# main_control.net
KiCad netlist of a schematic drawn in Altium Designer
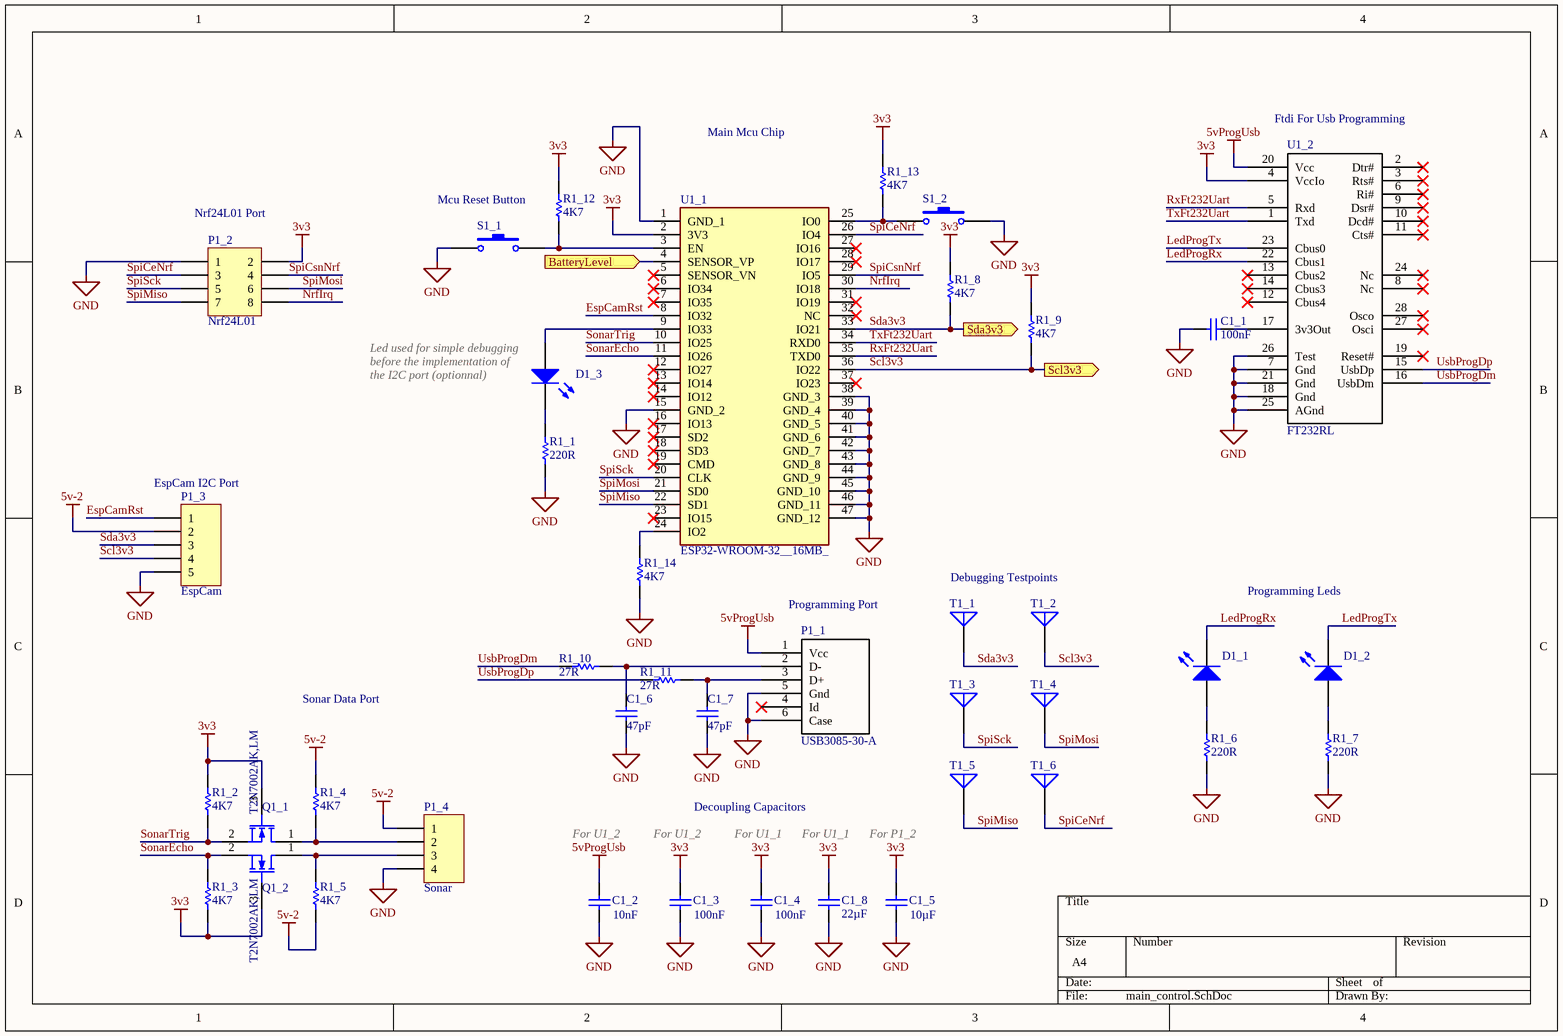
[diagram p0: main_control.SchDoc]

(export (version "E")
  (design (tool "Eeschema 10.0.6"))
  (components
    (comp (ref "C1_1")
      (value "100nF")
      (footprint "C1206")
      (description "Capacitor")
      (fields (field (name "Comment") "12063C104MAT2A") (field (name "PUBLISHER") "Altium Limited"))
      (libsource (lib "Miscellaneous Devices") (part "Cap"))
    )
    (comp (ref "C1_2")
      (value "10nF")
      (footprint "C1206")
      (description "Capacitor")
      (fields (field (name "Comment") "C1206C103M5RACTU") (field (name "PUBLISHER") "Altium Limited"))
      (libsource (lib "Miscellaneous Devices") (part "Cap"))
    )
    (comp (ref "C1_3")
      (value "100nF")
      (footprint "C1206")
      (description "Capacitor")
      (fields (field (name "Comment") "12063C104MAT2A") (field (name "PUBLISHER") "Altium Limited"))
      (libsource (lib "Miscellaneous Devices") (part "Cap"))
    )
    (comp (ref "C1_4")
      (value "100nF")
      (footprint "C1206")
      (description "Capacitor")
      (fields (field (name "Comment") "12063C104MAT2A") (field (name "PUBLISHER") "Altium Limited"))
      (libsource (lib "Miscellaneous Devices") (part "Cap"))
    )
    (comp (ref "C1_5")
      (value "10µF")
      (footprint "C1206")
      (description "Capacitor")
      (fields (field (name "Comment") "EMK316BJ106MLHT") (field (name "PUBLISHER") "Altium Limited"))
      (libsource (lib "Miscellaneous Devices") (part "Cap"))
    )
    (comp (ref "C1_6")
      (value "47pF")
      (footprint "C1206")
      (description "Capacitor")
      (fields (field (name "Comment") "CML1206C0G470JT50V") (field (name "PUBLISHER") "Altium Limited"))
      (libsource (lib "Miscellaneous Devices") (part "Cap"))
    )
    (comp (ref "C1_7")
      (value "47pF")
      (footprint "C1206")
      (description "Capacitor")
      (fields (field (name "Comment") "CML1206C0G470JT50V") (field (name "PUBLISHER") "Altium Limited"))
      (libsource (lib "Miscellaneous Devices") (part "Cap"))
    )
    (comp (ref "C1_8")
      (value "22µF")
      (footprint "C1206")
      (description "Capacitor")
      (fields (field (name "Comment") "CL31A226KOHNNNE") (field (name "PUBLISHER") "Altium Limited"))
      (libsource (lib "Miscellaneous Devices") (part "Cap"))
    )
    (comp (ref "D1_1")
      (value "LTST-C230KRKT")
      (footprint "C1206-POLARIZED")
      (description "Typical INFRARED GaAs LED")
      (fields (field (name "PUBLISHER") "Altium Limited"))
      (libsource (lib "Miscellaneous Devices") (part "LED0"))
    )
    (comp (ref "D1_2")
      (value "LTST-C230KRKT")
      (footprint "C1206-POLARIZED")
      (description "Typical INFRARED GaAs LED")
      (fields (field (name "PUBLISHER") "Altium Limited"))
      (libsource (lib "Miscellaneous Devices") (part "LED0"))
    )
    (comp (ref "D1_3")
      (value "APT3216QBC/D")
      (footprint "C1206-POLARIZED")
      (description "Typical INFRARED GaAs LED")
      (fields (field (name "PUBLISHER") "Altium Limited"))
      (libsource (lib "Miscellaneous Devices") (part "LED0"))
    )
    (comp (ref "P1_1")
      (value "USB3085-30-A")
      (footprint "USB-MICRO-CONNECTOR")
      (libsource (lib "projet_6e_session") (part "Usb Connector"))
    )
    (comp (ref "P1_2")
      (value "Nrf24L01")
      (footprint "HDR2X4-42")
      (description "Header, 4-Pin, Dual row")
      (fields (field (name "PUBLISHER") "Altium Limited"))
      (libsource (lib "Miscellaneous Connectors") (part "Header 4X2"))
    )
    (comp (ref "P1_3")
      (value "EspCam")
      (footprint "HDR1X5-42")
      (description "Header, 5-Pin")
      (fields (field (name "PUBLISHER") "Altium Limited"))
      (libsource (lib "Miscellaneous Connectors") (part "Header 5"))
    )
    (comp (ref "P1_4")
      (value "Sonar")
      (footprint "HDR1X4-42")
      (description "Header, 4-Pin")
      (fields (field (name "PUBLISHER") "Altium Limited"))
      (libsource (lib "Miscellaneous Connectors") (part "Header 4"))
    )
    (comp (ref "Q1_1")
      (value "T2N7002AK,LM")
      (footprint "SOT23_L")
      (description "N-Channel MOSFET")
      (fields (field (name "PUBLISHER") "Altium Limited"))
      (libsource (lib "Miscellaneous Devices") (part "MOSFET-N"))
    )
    (comp (ref "Q1_2")
      (value "T2N7002AK,LM")
      (footprint "SOT23_L")
      (description "N-Channel MOSFET")
      (fields (field (name "PUBLISHER") "Altium Limited"))
      (libsource (lib "Miscellaneous Devices") (part "MOSFET-N"))
    )
    (comp (ref "R1_1")
      (value "220R")
      (footprint "C1206")
      (description "Resistor")
      (fields (field (name "Comment") "Res1") (field (name "PUBLISHER") "Altium Limited"))
      (libsource (lib "Miscellaneous Devices") (part "Res1"))
    )
    (comp (ref "R1_2")
      (value "4K7")
      (footprint "C1206")
      (description "Resistor")
      (fields (field (name "Comment") "Res1") (field (name "PUBLISHER") "Altium Limited"))
      (libsource (lib "Miscellaneous Devices") (part "Res1"))
    )
    (comp (ref "R1_3")
      (value "4K7")
      (footprint "C1206")
      (description "Resistor")
      (fields (field (name "Comment") "Res1") (field (name "PUBLISHER") "Altium Limited"))
      (libsource (lib "Miscellaneous Devices") (part "Res1"))
    )
    (comp (ref "R1_4")
      (value "4K7")
      (footprint "C1206")
      (description "Resistor")
      (fields (field (name "Comment") "Res1") (field (name "PUBLISHER") "Altium Limited"))
      (libsource (lib "Miscellaneous Devices") (part "Res1"))
    )
    (comp (ref "R1_5")
      (value "4K7")
      (footprint "C1206")
      (description "Resistor")
      (fields (field (name "Comment") "Res1") (field (name "PUBLISHER") "Altium Limited"))
      (libsource (lib "Miscellaneous Devices") (part "Res1"))
    )
    (comp (ref "R1_6")
      (value "220R")
      (footprint "C1206")
      (description "Resistor")
      (fields (field (name "Comment") "Res1") (field (name "PUBLISHER") "Altium Limited"))
      (libsource (lib "Miscellaneous Devices") (part "Res1"))
    )
    (comp (ref "R1_7")
      (value "220R")
      (footprint "C1206")
      (description "Resistor")
      (fields (field (name "Comment") "Res1") (field (name "PUBLISHER") "Altium Limited"))
      (libsource (lib "Miscellaneous Devices") (part "Res1"))
    )
    (comp (ref "R1_8")
      (value "4K7")
      (footprint "C1206")
      (description "Resistor")
      (fields (field (name "Comment") "Res1") (field (name "PUBLISHER") "Altium Limited"))
      (libsource (lib "Miscellaneous Devices") (part "Res1"))
    )
    (comp (ref "R1_9")
      (value "4K7")
      (footprint "C1206")
      (description "Resistor")
      (fields (field (name "Comment") "Res1") (field (name "PUBLISHER") "Altium Limited"))
      (libsource (lib "Miscellaneous Devices") (part "Res1"))
    )
    (comp (ref "R1_10")
      (value "27R")
      (footprint "C1206")
      (description "Resistor")
      (fields (field (name "Comment") "Res1") (field (name "PUBLISHER") "Altium Limited"))
      (libsource (lib "Miscellaneous Devices") (part "Res1"))
    )
    (comp (ref "R1_11")
      (value "27R")
      (footprint "C1206")
      (description "Resistor")
      (fields (field (name "Comment") "Res1") (field (name "PUBLISHER") "Altium Limited"))
      (libsource (lib "Miscellaneous Devices") (part "Res1"))
    )
    (comp (ref "R1_12")
      (value "4K7")
      (footprint "C1206")
      (description "Resistor")
      (fields (field (name "Comment") "Res1") (field (name "PUBLISHER") "Altium Limited"))
      (libsource (lib "Miscellaneous Devices") (part "Res1"))
    )
    (comp (ref "R1_13")
      (value "4K7")
      (footprint "C1206")
      (description "Resistor")
      (fields (field (name "Comment") "Res1") (field (name "PUBLISHER") "Altium Limited"))
      (libsource (lib "Miscellaneous Devices") (part "Res1"))
    )
    (comp (ref "R1_14")
      (value "4K7")
      (footprint "C1206")
      (description "Resistor")
      (fields (field (name "Comment") "Res1") (field (name "PUBLISHER") "Altium Limited"))
      (libsource (lib "Miscellaneous Devices") (part "Res1"))
    )
    (comp (ref "S1_1")
      (value "FSM4LPASTR")
      (footprint "SW4-SMT")
      (description "Switch")
      (fields (field (name "PUBLISHER") "Altium Limited"))
      (libsource (lib "Miscellaneous Devices") (part "SW-PB"))
    )
    (comp (ref "S1_2")
      (value "FSM4LPASTR")
      (footprint "SW4-SMT")
      (description "Switch")
      (fields (field (name "PUBLISHER") "Altium Limited"))
      (libsource (lib "Miscellaneous Devices") (part "SW-PB"))
    )
    (comp (ref "T1_1")
      (value "Mounting Hole")
      (footprint "TESTPOINT")
      (description "Generic Antenna")
      (fields (field (name "PUBLISHER") "Altium Limited"))
      (libsource (lib "Miscellaneous Devices") (part "Antenna"))
    )
    (comp (ref "T1_2")
      (value "Mounting Hole")
      (footprint "TESTPOINT")
      (description "Generic Antenna")
      (fields (field (name "PUBLISHER") "Altium Limited"))
      (libsource (lib "Miscellaneous Devices") (part "Antenna"))
    )
    (comp (ref "T1_3")
      (value "Mounting Hole")
      (footprint "TESTPOINT")
      (description "Generic Antenna")
      (fields (field (name "PUBLISHER") "Altium Limited"))
      (libsource (lib "Miscellaneous Devices") (part "Antenna"))
    )
    (comp (ref "T1_4")
      (value "Mounting Hole")
      (footprint "TESTPOINT")
      (description "Generic Antenna")
      (fields (field (name "PUBLISHER") "Altium Limited"))
      (libsource (lib "Miscellaneous Devices") (part "Antenna"))
    )
    (comp (ref "T1_5")
      (value "Mounting Hole")
      (footprint "TESTPOINT")
      (description "Generic Antenna")
      (fields (field (name "PUBLISHER") "Altium Limited"))
      (libsource (lib "Miscellaneous Devices") (part "Antenna"))
    )
    (comp (ref "T1_6")
      (value "Mounting Hole")
      (footprint "TESTPOINT")
      (description "Generic Antenna")
      (fields (field (name "PUBLISHER") "Altium Limited"))
      (libsource (lib "Miscellaneous Devices") (part "Antenna"))
    )
    (comp (ref "U1_1")
      (value "ESP32-WROOM-32__16MB_")
      (footprint "ESP32WROOM32D16MB")
      (description "Integrated Circuit")
      (fields
        (field (name "MANUFACTURER_PART_NUMBER") "ESP32-WROOM-32 (16MB)")
        (field (name "MOUSER PART NUMBER") "356-ESPWROOM3216MB")
      )
      (libsource (lib "*") (part "ESP32-WROOM-32__16MB_"))
    )
    (comp (ref "U1_2")
      (value "FT232RL")
      (footprint "SOP65P778X200-28N")
      (libsource (lib "projet 6e session") (part "Ft232"))
    )
  )
  (nets
    (net (code "1") (name "/BatteryLevel") (class "Default")
      (node (ref "U1_1") (pin "4") (pinfunction "SENSOR_VP_4") (pintype "passive"))
    )
    (net (code "2") (name "/EspCamRst") (class "Default")
      (node (ref "P1_3") (pin "1") (pinfunction "1_1") (pintype "passive"))
      (node (ref "U1_1") (pin "8") (pinfunction "IO32_8") (pintype "passive"))
    )
    (net (code "3") (name "/LedProgRx") (class "Default")
      (node (ref "D1_1") (pin "2") (pinfunction "K_2") (pintype "passive"))
      (node (ref "U1_2") (pin "22") (pinfunction "Cbus1_22") (pintype "passive"))
    )
    (net (code "4") (name "/LedProgTx") (class "Default")
      (node (ref "D1_2") (pin "2") (pinfunction "K_2") (pintype "passive"))
      (node (ref "U1_2") (pin "23") (pinfunction "Cbus0_23") (pintype "passive"))
    )
    (net (code "5") (name "/NrfIrq") (class "Default")
      (node (ref "P1_2") (pin "8") (pinfunction "8_8") (pintype "passive"))
      (node (ref "U1_1") (pin "30") (pinfunction "IO18_30") (pintype "passive"))
    )
    (net (code "6") (name "/RxFt232Uart") (class "Default")
      (node (ref "U1_1") (pin "35") (pinfunction "TXD0_35") (pintype "passive"))
      (node (ref "U1_2") (pin "5") (pinfunction "Rxd_5") (pintype "passive"))
    )
    (net (code "7") (name "/Scl3v3") (class "Default")
      (node (ref "P1_3") (pin "4") (pinfunction "4_4") (pintype "passive"))
      (node (ref "R1_9") (pin "2") (pinfunction "2_2") (pintype "passive"))
      (node (ref "T1_2") (pin "1") (pinfunction "A_1") (pintype "passive"))
      (node (ref "U1_1") (pin "36") (pinfunction "IO22_36") (pintype "passive"))
    )
    (net (code "8") (name "/Sda3v3") (class "Default")
      (node (ref "P1_3") (pin "3") (pinfunction "3_3") (pintype "passive"))
      (node (ref "R1_8") (pin "2") (pinfunction "2_2") (pintype "passive"))
      (node (ref "T1_1") (pin "1") (pinfunction "A_1") (pintype "passive"))
      (node (ref "U1_1") (pin "33") (pinfunction "IO21_33") (pintype "passive"))
    )
    (net (code "9") (name "/SonarEcho") (class "Default")
      (node (ref "Q1_2") (pin "2") (pinfunction "S_2") (pintype "passive"))
      (node (ref "R1_3") (pin "1") (pinfunction "1_1") (pintype "passive"))
      (node (ref "U1_1") (pin "11") (pinfunction "IO26_11") (pintype "passive"))
    )
    (net (code "10") (name "/SonarTrig") (class "Default")
      (node (ref "Q1_1") (pin "2") (pinfunction "S_2") (pintype "passive"))
      (node (ref "R1_2") (pin "2") (pinfunction "2_2") (pintype "passive"))
      (node (ref "U1_1") (pin "10") (pinfunction "IO25_10") (pintype "passive"))
    )
    (net (code "11") (name "/SpiCeNrf") (class "Default")
      (node (ref "P1_2") (pin "3") (pinfunction "3_3") (pintype "passive"))
      (node (ref "T1_6") (pin "1") (pinfunction "A_1") (pintype "passive"))
      (node (ref "U1_1") (pin "26") (pinfunction "IO4_26") (pintype "passive"))
    )
    (net (code "12") (name "/SpiCsnNrf") (class "Default")
      (node (ref "P1_2") (pin "4") (pinfunction "4_4") (pintype "passive"))
      (node (ref "U1_1") (pin "29") (pinfunction "IO5_29") (pintype "passive"))
    )
    (net (code "13") (name "/SpiMiso") (class "Default")
      (node (ref "P1_2") (pin "7") (pinfunction "7_7") (pintype "passive"))
      (node (ref "T1_5") (pin "1") (pinfunction "A_1") (pintype "passive"))
      (node (ref "U1_1") (pin "22") (pinfunction "SD1_22") (pintype "passive"))
    )
    (net (code "14") (name "/SpiMosi") (class "Default")
      (node (ref "P1_2") (pin "6") (pinfunction "6_6") (pintype "passive"))
      (node (ref "T1_4") (pin "1") (pinfunction "A_1") (pintype "passive"))
      (node (ref "U1_1") (pin "21") (pinfunction "SD0_21") (pintype "passive"))
    )
    (net (code "15") (name "/SpiSck") (class "Default")
      (node (ref "P1_2") (pin "5") (pinfunction "5_5") (pintype "passive"))
      (node (ref "T1_3") (pin "1") (pinfunction "A_1") (pintype "passive"))
      (node (ref "U1_1") (pin "20") (pinfunction "CLK_20") (pintype "passive"))
    )
    (net (code "16") (name "/TxFt232Uart") (class "Default")
      (node (ref "U1_1") (pin "34") (pinfunction "RXD0_34") (pintype "passive"))
      (node (ref "U1_2") (pin "1") (pinfunction "Txd_1") (pintype "passive"))
    )
    (net (code "17") (name "/UsbProgDm") (class "Default")
      (node (ref "R1_10") (pin "1") (pinfunction "1_1") (pintype "passive"))
      (node (ref "U1_2") (pin "16") (pinfunction "UsbDm_16") (pintype "passive"))
    )
    (net (code "18") (name "/UsbProgDp") (class "Default")
      (node (ref "R1_11") (pin "1") (pinfunction "1_1") (pintype "passive"))
      (node (ref "U1_2") (pin "15") (pinfunction "UsbDp_15") (pintype "passive"))
    )
    (net (code "19") (name "3v3") (class "Default")
      (node (ref "C1_3") (pin "1") (pinfunction "1_1") (pintype "passive"))
      (node (ref "C1_4") (pin "1") (pinfunction "1_1") (pintype "passive"))
      (node (ref "C1_5") (pin "1") (pinfunction "1_1") (pintype "passive"))
      (node (ref "C1_8") (pin "1") (pinfunction "1_1") (pintype "passive"))
      (node (ref "P1_2") (pin "2") (pinfunction "2_2") (pintype "passive"))
      (node (ref "Q1_1") (pin "3") (pinfunction "G_3") (pintype "passive"))
      (node (ref "Q1_2") (pin "3") (pinfunction "G_3") (pintype "passive"))
      (node (ref "R1_12") (pin "2") (pinfunction "2_2") (pintype "passive"))
      (node (ref "R1_13") (pin "1") (pinfunction "1_1") (pintype "passive"))
      (node (ref "R1_2") (pin "1") (pinfunction "1_1") (pintype "passive"))
      (node (ref "R1_3") (pin "2") (pinfunction "2_2") (pintype "passive"))
      (node (ref "R1_8") (pin "1") (pinfunction "1_1") (pintype "passive"))
      (node (ref "R1_9") (pin "1") (pinfunction "1_1") (pintype "passive"))
      (node (ref "U1_1") (pin "2") (pinfunction "3V3_2") (pintype "passive"))
      (node (ref "U1_2") (pin "4") (pinfunction "VccIo_4") (pintype "passive"))
    )
    (net (code "20") (name "5v-2") (class "Default")
      (node (ref "P1_3") (pin "2") (pinfunction "2_2") (pintype "passive"))
      (node (ref "P1_4") (pin "1") (pinfunction "1_1") (pintype "passive"))
      (node (ref "R1_4") (pin "1") (pinfunction "1_1") (pintype "passive"))
      (node (ref "R1_5") (pin "2") (pinfunction "2_2") (pintype "passive"))
    )
    (net (code "21") (name "5vProgUsb") (class "Default")
      (node (ref "C1_2") (pin "1") (pinfunction "1_1") (pintype "passive"))
      (node (ref "P1_1") (pin "1") (pinfunction "Vcc_1") (pintype "passive"))
      (node (ref "U1_2") (pin "20") (pinfunction "Vcc_20") (pintype "passive"))
    )
    (net (code "22") (name "GND") (class "Default")
      (node (ref "C1_1") (pin "2") (pinfunction "2_2") (pintype "passive"))
      (node (ref "C1_2") (pin "2") (pinfunction "2_2") (pintype "passive"))
      (node (ref "C1_3") (pin "2") (pinfunction "2_2") (pintype "passive"))
      (node (ref "C1_4") (pin "2") (pinfunction "2_2") (pintype "passive"))
      (node (ref "C1_5") (pin "2") (pinfunction "2_2") (pintype "passive"))
      (node (ref "C1_6") (pin "1") (pinfunction "1_1") (pintype "passive"))
      (node (ref "C1_7") (pin "2") (pinfunction "2_2") (pintype "passive"))
      (node (ref "C1_8") (pin "2") (pinfunction "2_2") (pintype "passive"))
      (node (ref "P1_1") (pin "5") (pinfunction "Gnd_5") (pintype "passive"))
      (node (ref "P1_1") (pin "6") (pinfunction "Case_6") (pintype "passive"))
      (node (ref "P1_2") (pin "1") (pinfunction "1_1") (pintype "passive"))
      (node (ref "P1_3") (pin "5") (pinfunction "5_5") (pintype "passive"))
      (node (ref "P1_4") (pin "4") (pinfunction "4_4") (pintype "passive"))
      (node (ref "R1_1") (pin "2") (pinfunction "2_2") (pintype "passive"))
      (node (ref "R1_14") (pin "2") (pinfunction "2_2") (pintype "passive"))
      (node (ref "R1_6") (pin "2") (pinfunction "2_2") (pintype "passive"))
      (node (ref "R1_7") (pin "2") (pinfunction "2_2") (pintype "passive"))
      (node (ref "S1_1") (pin "1") (pinfunction "1_1") (pintype "passive"))
      (node (ref "S1_2") (pin "2") (pinfunction "2_2") (pintype "passive"))
      (node (ref "U1_1") (pin "1") (pinfunction "GND_1_1") (pintype "passive"))
      (node (ref "U1_1") (pin "15") (pinfunction "GND_2_15") (pintype "passive"))
      (node (ref "U1_1") (pin "38") (pinfunction "GND_3_38") (pintype "passive"))
      (node (ref "U1_1") (pin "39") (pinfunction "GND_4_39") (pintype "passive"))
      (node (ref "U1_1") (pin "40") (pinfunction "GND_5_40") (pintype "passive"))
      (node (ref "U1_1") (pin "41") (pinfunction "GND_6_41") (pintype "passive"))
      (node (ref "U1_1") (pin "42") (pinfunction "GND_7_42") (pintype "passive"))
      (node (ref "U1_1") (pin "43") (pinfunction "GND_8_43") (pintype "passive"))
      (node (ref "U1_1") (pin "44") (pinfunction "GND_9_44") (pintype "passive"))
      (node (ref "U1_1") (pin "45") (pinfunction "GND_10_45") (pintype "passive"))
      (node (ref "U1_1") (pin "46") (pinfunction "GND_11_46") (pintype "passive"))
      (node (ref "U1_1") (pin "47") (pinfunction "GND_12_47") (pintype "passive"))
      (node (ref "U1_2") (pin "18") (pinfunction "Gnd_18") (pintype "passive"))
      (node (ref "U1_2") (pin "21") (pinfunction "Gnd_21") (pintype "passive"))
      (node (ref "U1_2") (pin "25") (pinfunction "AGnd_25") (pintype "passive"))
      (node (ref "U1_2") (pin "26") (pinfunction "Test_26") (pintype "passive"))
      (node (ref "U1_2") (pin "7") (pinfunction "Gnd_7") (pintype "passive"))
    )
    (net (code "23") (name "Net-(D1_1-A)") (class "Default")
      (node (ref "D1_1") (pin "1") (pinfunction "A_1") (pintype "passive"))
      (node (ref "R1_6") (pin "1") (pinfunction "1_1") (pintype "passive"))
    )
    (net (code "24") (name "Net-(D1_2-A)") (class "Default")
      (node (ref "D1_2") (pin "1") (pinfunction "A_1") (pintype "passive"))
      (node (ref "R1_7") (pin "1") (pinfunction "1_1") (pintype "passive"))
    )
    (net (code "25") (name "Net-(D1_3-A)") (class "Default")
      (node (ref "D1_3") (pin "1") (pinfunction "A_1") (pintype "passive"))
      (node (ref "U1_1") (pin "9") (pinfunction "IO33_9") (pintype "passive"))
    )
    (net (code "26") (name "Net-(D1_3-K)") (class "Default")
      (node (ref "D1_3") (pin "2") (pinfunction "K_2") (pintype "passive"))
      (node (ref "R1_1") (pin "1") (pinfunction "1_1") (pintype "passive"))
    )
    (net (code "27") (name "Net-(P1_1-D+)") (class "Default")
      (node (ref "C1_7") (pin "1") (pinfunction "1_1") (pintype "passive"))
      (node (ref "P1_1") (pin "3") (pinfunction "D+_3") (pintype "passive"))
      (node (ref "R1_11") (pin "2") (pinfunction "2_2") (pintype "passive"))
    )
    (net (code "28") (name "Net-(P1_1-D-)") (class "Default")
      (node (ref "C1_6") (pin "2") (pinfunction "2_2") (pintype "passive"))
      (node (ref "P1_1") (pin "2") (pinfunction "D-_2") (pintype "passive"))
      (node (ref "R1_10") (pin "2") (pinfunction "2_2") (pintype "passive"))
    )
    (net (code "29") (name "Net-(Q1_1-D)") (class "Default")
      (node (ref "P1_4") (pin "2") (pinfunction "2_2") (pintype "passive"))
      (node (ref "Q1_1") (pin "1") (pinfunction "D_1") (pintype "passive"))
      (node (ref "R1_4") (pin "2") (pinfunction "2_2") (pintype "passive"))
    )
    (net (code "30") (name "Net-(Q1_2-D)") (class "Default")
      (node (ref "P1_4") (pin "3") (pinfunction "3_3") (pintype "passive"))
      (node (ref "Q1_2") (pin "1") (pinfunction "D_1") (pintype "passive"))
      (node (ref "R1_5") (pin "1") (pinfunction "1_1") (pintype "passive"))
    )
    (net (code "31") (name "Net-(U1_1-EN)") (class "Default")
      (node (ref "R1_12") (pin "1") (pinfunction "1_1") (pintype "passive"))
      (node (ref "S1_1") (pin "2") (pinfunction "2_2") (pintype "passive"))
      (node (ref "U1_1") (pin "3") (pinfunction "EN_3") (pintype "passive"))
    )
    (net (code "32") (name "Net-(U1_1-IO0)") (class "Default")
      (node (ref "R1_13") (pin "2") (pinfunction "2_2") (pintype "passive"))
      (node (ref "S1_2") (pin "1") (pinfunction "1_1") (pintype "passive"))
      (node (ref "U1_1") (pin "25") (pinfunction "IO0_25") (pintype "passive"))
    )
    (net (code "33") (name "Net-(U1_1-IO2)") (class "Default")
      (node (ref "R1_14") (pin "1") (pinfunction "1_1") (pintype "passive"))
      (node (ref "U1_1") (pin "24") (pinfunction "IO2_24") (pintype "passive"))
    )
    (net (code "34") (name "Net-(U1_2-3v3Out)") (class "Default")
      (node (ref "C1_1") (pin "1") (pinfunction "1_1") (pintype "passive"))
      (node (ref "U1_2") (pin "17") (pinfunction "3v3Out_17") (pintype "passive"))
    )
    (net (code "35") (name "unconnected-(P1_1-Id-Pad4)") (class "Default")
      (node (ref "P1_1") (pin "4") (pinfunction "Id_4") (pintype "passive+no_connect"))
    )
    (net (code "36") (name "unconnected-(U1_1-CMD-Pad19)") (class "Default")
      (node (ref "U1_1") (pin "19") (pinfunction "CMD_19") (pintype "passive+no_connect"))
    )
    (net (code "37") (name "unconnected-(U1_1-IO12-Pad14)") (class "Default")
      (node (ref "U1_1") (pin "14") (pinfunction "IO12_14") (pintype "passive+no_connect"))
    )
    (net (code "38") (name "unconnected-(U1_1-IO13-Pad16)") (class "Default")
      (node (ref "U1_1") (pin "16") (pinfunction "IO13_16") (pintype "passive+no_connect"))
    )
    (net (code "39") (name "unconnected-(U1_1-IO14-Pad13)") (class "Default")
      (node (ref "U1_1") (pin "13") (pinfunction "IO14_13") (pintype "passive+no_connect"))
    )
    (net (code "40") (name "unconnected-(U1_1-IO15-Pad23)") (class "Default")
      (node (ref "U1_1") (pin "23") (pinfunction "IO15_23") (pintype "passive+no_connect"))
    )
    (net (code "41") (name "unconnected-(U1_1-IO16-Pad27)") (class "Default")
      (node (ref "U1_1") (pin "27") (pinfunction "IO16_27") (pintype "passive+no_connect"))
    )
    (net (code "42") (name "unconnected-(U1_1-IO17-Pad28)") (class "Default")
      (node (ref "U1_1") (pin "28") (pinfunction "IO17_28") (pintype "passive+no_connect"))
    )
    (net (code "43") (name "unconnected-(U1_1-IO19-Pad31)") (class "Default")
      (node (ref "U1_1") (pin "31") (pinfunction "IO19_31") (pintype "passive+no_connect"))
    )
    (net (code "44") (name "unconnected-(U1_1-IO23-Pad37)") (class "Default")
      (node (ref "U1_1") (pin "37") (pinfunction "IO23_37") (pintype "passive+no_connect"))
    )
    (net (code "45") (name "unconnected-(U1_1-IO27-Pad12)") (class "Default")
      (node (ref "U1_1") (pin "12") (pinfunction "IO27_12") (pintype "passive+no_connect"))
    )
    (net (code "46") (name "unconnected-(U1_1-IO34-Pad6)") (class "Default")
      (node (ref "U1_1") (pin "6") (pinfunction "IO34_6") (pintype "passive+no_connect"))
    )
    (net (code "47") (name "unconnected-(U1_1-IO35-Pad7)") (class "Default")
      (node (ref "U1_1") (pin "7") (pinfunction "IO35_7") (pintype "passive+no_connect"))
    )
    (net (code "48") (name "unconnected-(U1_1-NC-Pad32)") (class "Default")
      (node (ref "U1_1") (pin "32") (pinfunction "NC_32") (pintype "passive+no_connect"))
    )
    (net (code "49") (name "unconnected-(U1_1-SD2-Pad17)") (class "Default")
      (node (ref "U1_1") (pin "17") (pinfunction "SD2_17") (pintype "passive+no_connect"))
    )
    (net (code "50") (name "unconnected-(U1_1-SD3-Pad18)") (class "Default")
      (node (ref "U1_1") (pin "18") (pinfunction "SD3_18") (pintype "passive+no_connect"))
    )
    (net (code "51") (name "unconnected-(U1_1-SENSOR_VN-Pad5)") (class "Default")
      (node (ref "U1_1") (pin "5") (pinfunction "SENSOR_VN_5") (pintype "passive+no_connect"))
    )
    (net (code "52") (name "unconnected-(U1_2-Cbus2-Pad13)") (class "Default")
      (node (ref "U1_2") (pin "13") (pinfunction "Cbus2_13") (pintype "passive+no_connect"))
    )
    (net (code "53") (name "unconnected-(U1_2-Cbus3-Pad14)") (class "Default")
      (node (ref "U1_2") (pin "14") (pinfunction "Cbus3_14") (pintype "passive+no_connect"))
    )
    (net (code "54") (name "unconnected-(U1_2-Cbus4-Pad12)") (class "Default")
      (node (ref "U1_2") (pin "12") (pinfunction "Cbus4_12") (pintype "passive+no_connect"))
    )
    (net (code "55") (name "unconnected-(U1_2-Cts#-Pad11)") (class "Default")
      (node (ref "U1_2") (pin "11") (pinfunction "Cts#_11") (pintype "passive+no_connect"))
    )
    (net (code "56") (name "unconnected-(U1_2-Dcd#-Pad10)") (class "Default")
      (node (ref "U1_2") (pin "10") (pinfunction "Dcd#_10") (pintype "passive+no_connect"))
    )
    (net (code "57") (name "unconnected-(U1_2-Dsr#-Pad9)") (class "Default")
      (node (ref "U1_2") (pin "9") (pinfunction "Dsr#_9") (pintype "passive+no_connect"))
    )
    (net (code "58") (name "unconnected-(U1_2-Dtr#-Pad2)") (class "Default")
      (node (ref "U1_2") (pin "2") (pinfunction "Dtr#_2") (pintype "passive+no_connect"))
    )
    (net (code "59") (name "unconnected-(U1_2-Nc-Pad8)") (class "Default")
      (node (ref "U1_2") (pin "8") (pinfunction "Nc_8") (pintype "passive+no_connect"))
    )
    (net (code "60") (name "unconnected-(U1_2-Nc-Pad24)") (class "Default")
      (node (ref "U1_2") (pin "24") (pinfunction "Nc_24") (pintype "passive+no_connect"))
    )
    (net (code "61") (name "unconnected-(U1_2-Osci-Pad27)") (class "Default")
      (node (ref "U1_2") (pin "27") (pinfunction "Osci_27") (pintype "passive+no_connect"))
    )
    (net (code "62") (name "unconnected-(U1_2-Osco-Pad28)") (class "Default")
      (node (ref "U1_2") (pin "28") (pinfunction "Osco_28") (pintype "passive+no_connect"))
    )
    (net (code "63") (name "unconnected-(U1_2-Reset#-Pad19)") (class "Default")
      (node (ref "U1_2") (pin "19") (pinfunction "Reset#_19") (pintype "passive+no_connect"))
    )
    (net (code "64") (name "unconnected-(U1_2-Ri#-Pad6)") (class "Default")
      (node (ref "U1_2") (pin "6") (pinfunction "Ri#_6") (pintype "passive+no_connect"))
    )
    (net (code "65") (name "unconnected-(U1_2-Rts#-Pad3)") (class "Default")
      (node (ref "U1_2") (pin "3") (pinfunction "Rts#_3") (pintype "passive+no_connect"))
    )
  )
)
